# PROYEK.net
KiCad netlist of a schematic drawn in EAGLE
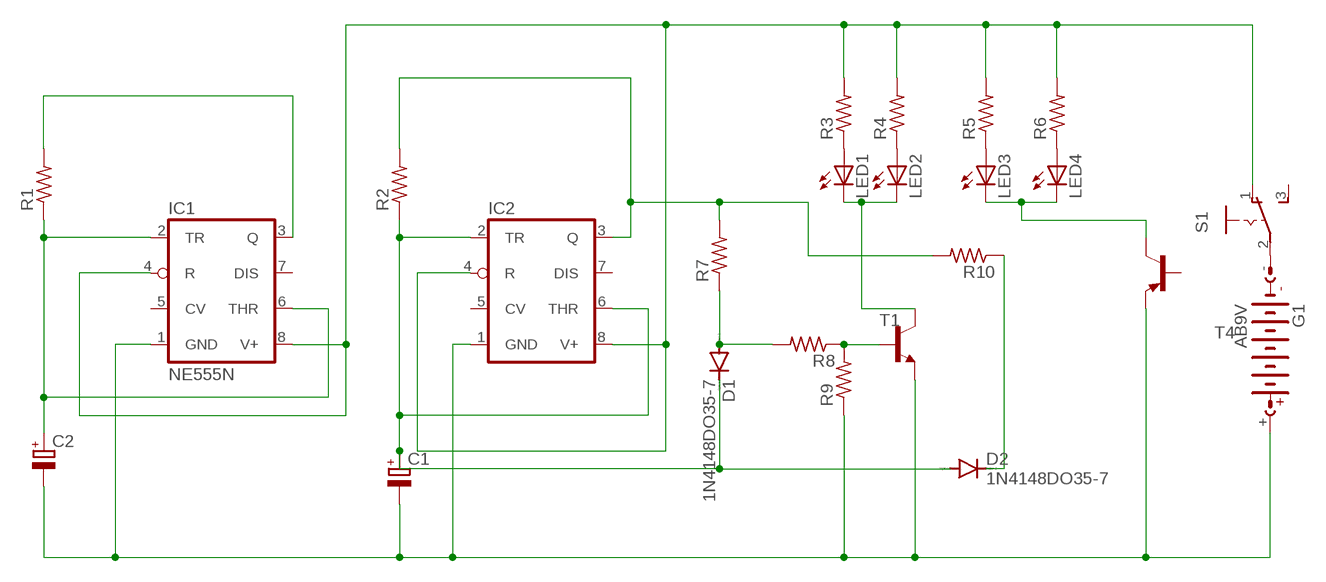
[diagram p0: schematic, sheet 1]

(export (version "E")
  (design (tool "Eeschema 10.0.6"))
  (components
    (comp (ref "C1")
      (value "CPOL-EUE3.5-8")
      (footprint "eagle-import:E3,5-8")
      (libsource (lib "eagle-import") (part "CPOL-EUE3.5-8"))
    )
    (comp (ref "C2")
      (value "CPOL-EUE3.5-10")
      (footprint "eagle-import:E3,5-10")
      (libsource (lib "eagle-import") (part "CPOL-EUE3.5-10"))
    )
    (comp (ref "D1")
      (value "1N4148DO35-7")
      (footprint "eagle-import:DO35-7")
      (libsource (lib "eagle-import") (part "1N4148DO35-7"))
    )
    (comp (ref "D2")
      (value "1N4148DO35-7")
      (footprint "eagle-import:DO35-7")
      (libsource (lib "eagle-import") (part "1N4148DO35-7"))
    )
    (comp (ref "G1")
      (value "AB9V")
      (footprint "eagle-import:AB9V")
      (libsource (lib "eagle-import") (part "AB9V"))
    )
    (comp (ref "IC1")
      (value "NE555N")
      (footprint "eagle-import:DIL08")
      (libsource (lib "eagle-import") (part "555NNE"))
    )
    (comp (ref "IC2")
      (value "NE555N")
      (footprint "eagle-import:DIL08")
      (libsource (lib "eagle-import") (part "555NNE"))
    )
    (comp (ref "LED1")
      (value "LED5MM")
      (footprint "eagle-import:LED5MM")
      (libsource (lib "eagle-import") (part "LED5MM"))
    )
    (comp (ref "LED2")
      (value "LED5MM")
      (footprint "eagle-import:LED5MM")
      (libsource (lib "eagle-import") (part "LED5MM"))
    )
    (comp (ref "LED3")
      (value "LED5MM")
      (footprint "eagle-import:LED5MM")
      (libsource (lib "eagle-import") (part "LED5MM"))
    )
    (comp (ref "LED4")
      (value "LED5MM")
      (footprint "eagle-import:LED5MM")
      (libsource (lib "eagle-import") (part "LED5MM"))
    )
    (comp (ref "R1")
      (value "R-US_0204/2V")
      (footprint "eagle-import:0204V")
      (libsource (lib "eagle-import") (part "R-US_0204/2V"))
    )
    (comp (ref "R2")
      (value "R-US_0204/2V")
      (footprint "eagle-import:0204V")
      (libsource (lib "eagle-import") (part "R-US_0204/2V"))
    )
    (comp (ref "R3")
      (value "R-US_0204/7")
      (footprint "eagle-import:0204_7")
      (libsource (lib "eagle-import") (part "R-US_0204/7"))
    )
    (comp (ref "R4")
      (value "R-US_0204/7")
      (footprint "eagle-import:0204_7")
      (libsource (lib "eagle-import") (part "R-US_0204/7"))
    )
    (comp (ref "R5")
      (value "R-US_0204/7")
      (footprint "eagle-import:0204_7")
      (libsource (lib "eagle-import") (part "R-US_0204/7"))
    )
    (comp (ref "R6")
      (value "R-US_0204/7")
      (footprint "eagle-import:0204_7")
      (libsource (lib "eagle-import") (part "R-US_0204/7"))
    )
    (comp (ref "R7")
      (value "R-US_0204/7")
      (footprint "eagle-import:0204_7")
      (libsource (lib "eagle-import") (part "R-US_0204/7"))
    )
    (comp (ref "R8")
      (value "R-US_0204/7")
      (footprint "eagle-import:0204_7")
      (libsource (lib "eagle-import") (part "R-US_0204/7"))
    )
    (comp (ref "R9")
      (value "R-US_0204/7")
      (footprint "eagle-import:0204_7")
      (libsource (lib "eagle-import") (part "R-US_0204/7"))
    )
    (comp (ref "R10")
      (value "R-US_0204/7")
      (footprint "eagle-import:0204_7")
      (libsource (lib "eagle-import") (part "R-US_0204/7"))
    )
    (comp (ref "S1")
      (value "255SB")
      (footprint "eagle-import:255SB")
      (libsource (lib "eagle-import") (part "255SB"))
    )
    (comp (ref "T1")
      (value "BC547-NPN-TO92-CBE")
      (footprint "eagle-import:TO92-CBE")
      (libsource (lib "eagle-import") (part "-NPN-TO92-CBEBC547"))
    )
    (comp (ref "T4")
      (value "BC557C-PNP-TO92-EBC")
      (footprint "eagle-import:TO92-EBC")
      (libsource (lib "eagle-import") (part "-PNP-TO92-EBCBC557C"))
    )
  )
  (nets
    (net (code "1") (name "Net-(D1-PadA)") (class "Default")
      (node (ref "D1") (pin "A") (pinfunction "A_A") (pintype "passive"))
      (node (ref "R7") (pin "1") (pinfunction "1_1") (pintype "passive"))
      (node (ref "R8") (pin "2") (pinfunction "2_2") (pintype "passive"))
    )
    (net (code "2") (name "Net-(D2-PadC)") (class "Default")
      (node (ref "D2") (pin "C") (pinfunction "C_C") (pintype "passive"))
      (node (ref "R10") (pin "1") (pinfunction "1_1") (pintype "passive"))
    )
    (net (code "3") (name "Net-(IC1-GND)") (class "Default")
      (node (ref "C1") (pin "-") (pinfunction "-_-") (pintype "passive"))
      (node (ref "C2") (pin "-") (pinfunction "-_-") (pintype "passive"))
      (node (ref "G1") (pin "+") (pinfunction "+_+") (pintype "passive"))
      (node (ref "IC1") (pin "1") (pinfunction "GND_1") (pintype "power_in"))
      (node (ref "IC2") (pin "1") (pinfunction "GND_1") (pintype "power_in"))
      (node (ref "R9") (pin "1") (pinfunction "1_1") (pintype "passive"))
      (node (ref "T1") (pin "E") (pinfunction "E_E") (pintype "passive"))
      (node (ref "T4") (pin "E") (pinfunction "E_E") (pintype "passive"))
    )
    (net (code "4") (name "Net-(IC1-Q)") (class "Default")
      (node (ref "IC1") (pin "3") (pinfunction "Q_3") (pintype "output"))
      (node (ref "R1") (pin "2") (pinfunction "2_2") (pintype "passive"))
    )
    (net (code "5") (name "Net-(IC1-R)") (class "Default")
      (node (ref "IC1") (pin "4") (pinfunction "R_4") (pintype "input"))
      (node (ref "IC1") (pin "8") (pinfunction "V+_8") (pintype "power_in"))
      (node (ref "IC2") (pin "4") (pinfunction "R_4") (pintype "input"))
      (node (ref "IC2") (pin "8") (pinfunction "V+_8") (pintype "power_in"))
      (node (ref "R3") (pin "2") (pinfunction "2_2") (pintype "passive"))
      (node (ref "R4") (pin "2") (pinfunction "2_2") (pintype "passive"))
      (node (ref "R5") (pin "2") (pinfunction "2_2") (pintype "passive"))
      (node (ref "R6") (pin "2") (pinfunction "2_2") (pintype "passive"))
      (node (ref "S1") (pin "1") (pinfunction "O_1") (pintype "passive"))
    )
    (net (code "6") (name "Net-(IC1-THR)") (class "Default")
      (node (ref "C2") (pin "+") (pinfunction "+_+") (pintype "passive"))
      (node (ref "IC1") (pin "2") (pinfunction "TR_2") (pintype "input"))
      (node (ref "IC1") (pin "6") (pinfunction "THR_6") (pintype "input"))
      (node (ref "R1") (pin "1") (pinfunction "1_1") (pintype "passive"))
    )
    (net (code "7") (name "Net-(IC2-Q)") (class "Default")
      (node (ref "IC2") (pin "3") (pinfunction "Q_3") (pintype "output"))
      (node (ref "R10") (pin "2") (pinfunction "2_2") (pintype "passive"))
      (node (ref "R2") (pin "2") (pinfunction "2_2") (pintype "passive"))
      (node (ref "R7") (pin "2") (pinfunction "2_2") (pintype "passive"))
    )
    (net (code "8") (name "Net-(IC2-THR)") (class "Default")
      (node (ref "C1") (pin "+") (pinfunction "+_+") (pintype "passive"))
      (node (ref "D1") (pin "C") (pinfunction "C_C") (pintype "passive"))
      (node (ref "D2") (pin "A") (pinfunction "A_A") (pintype "passive"))
      (node (ref "IC2") (pin "2") (pinfunction "TR_2") (pintype "input"))
      (node (ref "IC2") (pin "6") (pinfunction "THR_6") (pintype "input"))
      (node (ref "R2") (pin "1") (pinfunction "1_1") (pintype "passive"))
    )
    (net (code "9") (name "Net-(LED1-C)") (class "Default")
      (node (ref "LED1") (pin "K") (pinfunction "C_K") (pintype "passive"))
      (node (ref "LED2") (pin "K") (pinfunction "C_K") (pintype "passive"))
      (node (ref "T1") (pin "C") (pinfunction "C_C") (pintype "passive"))
    )
    (net (code "10") (name "Net-(LED1-PadA)") (class "Default")
      (node (ref "LED1") (pin "A") (pinfunction "A_A") (pintype "passive"))
      (node (ref "R3") (pin "1") (pinfunction "1_1") (pintype "passive"))
    )
    (net (code "11") (name "Net-(LED2-PadA)") (class "Default")
      (node (ref "LED2") (pin "A") (pinfunction "A_A") (pintype "passive"))
      (node (ref "R4") (pin "1") (pinfunction "1_1") (pintype "passive"))
    )
    (net (code "12") (name "Net-(LED3-C)") (class "Default")
      (node (ref "LED3") (pin "K") (pinfunction "C_K") (pintype "passive"))
      (node (ref "LED4") (pin "K") (pinfunction "C_K") (pintype "passive"))
      (node (ref "T4") (pin "C") (pinfunction "C_C") (pintype "passive"))
    )
    (net (code "13") (name "Net-(LED3-PadA)") (class "Default")
      (node (ref "LED3") (pin "A") (pinfunction "A_A") (pintype "passive"))
      (node (ref "R5") (pin "1") (pinfunction "1_1") (pintype "passive"))
    )
    (net (code "14") (name "Net-(LED4-PadA)") (class "Default")
      (node (ref "LED4") (pin "A") (pinfunction "A_A") (pintype "passive"))
      (node (ref "R6") (pin "1") (pinfunction "1_1") (pintype "passive"))
    )
    (net (code "15") (name "Net-(R8-Pad1)") (class "Default")
      (node (ref "R8") (pin "1") (pinfunction "1_1") (pintype "passive"))
      (node (ref "R9") (pin "2") (pinfunction "2_2") (pintype "passive"))
      (node (ref "T1") (pin "B") (pinfunction "B_B") (pintype "passive"))
    )
    (net (code "16") (name "Net-(S1-P)") (class "Default")
      (node (ref "G1") (pin "-") (pinfunction "-_-") (pintype "passive"))
      (node (ref "S1") (pin "2") (pinfunction "P_2") (pintype "passive"))
    )
    (net (code "17") (name "unconnected-(IC1-CV-Pad5)") (class "Default")
      (node (ref "IC1") (pin "5") (pinfunction "CV_5") (pintype "input"))
    )
    (net (code "18") (name "unconnected-(IC1-DIS-Pad7)") (class "Default")
      (node (ref "IC1") (pin "7") (pinfunction "DIS_7") (pintype "input"))
    )
    (net (code "19") (name "unconnected-(IC2-CV-Pad5)") (class "Default")
      (node (ref "IC2") (pin "5") (pinfunction "CV_5") (pintype "input"))
    )
    (net (code "20") (name "unconnected-(IC2-DIS-Pad7)") (class "Default")
      (node (ref "IC2") (pin "7") (pinfunction "DIS_7") (pintype "input"))
    )
    (net (code "21") (name "unconnected-(S1-S-Pad3)") (class "Default")
      (node (ref "S1") (pin "3") (pinfunction "S_3") (pintype "passive"))
    )
    (net (code "22") (name "unconnected-(T4-PadB)") (class "Default")
      (node (ref "T4") (pin "B") (pinfunction "B_B") (pintype "passive"))
    )
  )
)
